# telemetria.net
KiCad netlist of a schematic drawn in EAGLE
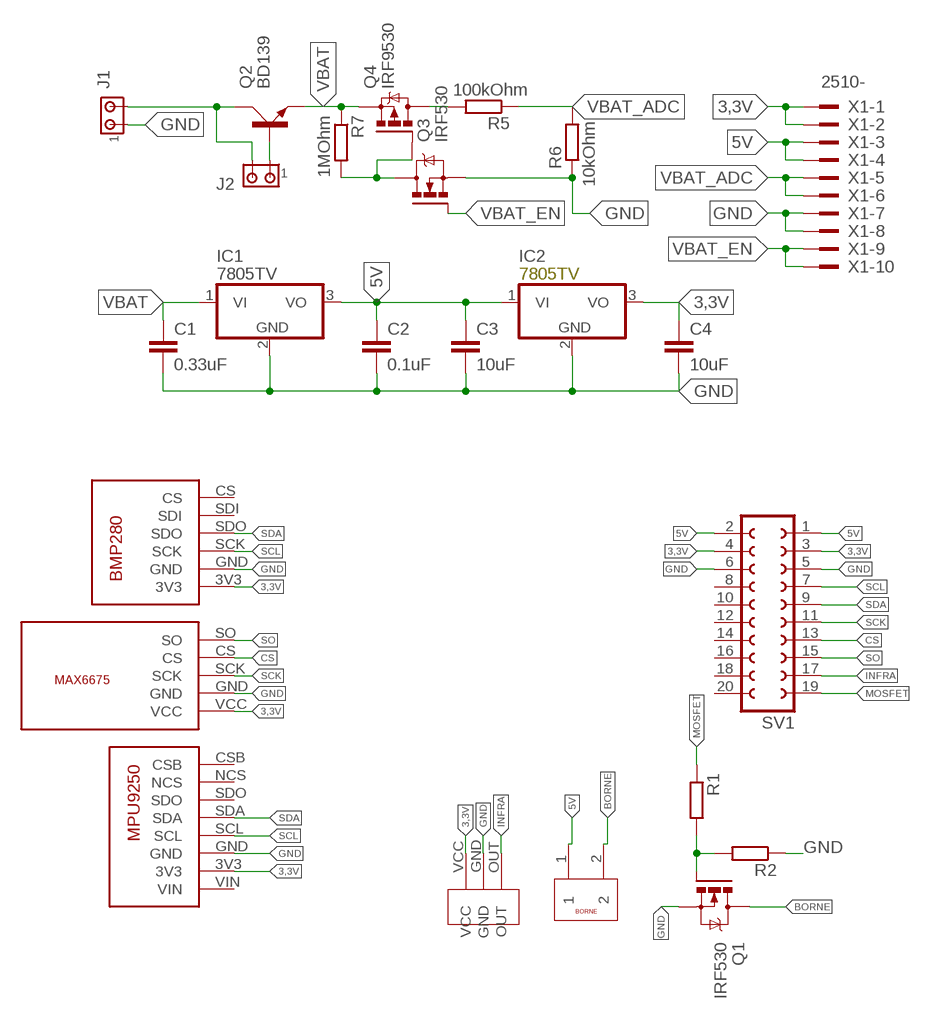
[diagram p0: schematic, sheet 1]

(export (version "E")
  (design (tool "Eeschema 10.0.6"))
  (components
    (comp (ref "C1")
      (value "0.33uF")
      (footprint "eagle-import:C2.5-3")
      (libsource (lib "eagle-import") (part "C2,5-3"))
    )
    (comp (ref "C2")
      (value "0.1uF")
      (footprint "eagle-import:C2.5-3")
      (libsource (lib "eagle-import") (part "C2,5-3"))
    )
    (comp (ref "C3")
      (value "10uF")
      (footprint "eagle-import:C2.5-3")
      (libsource (lib "eagle-import") (part "C2,5-3"))
    )
    (comp (ref "C4")
      (value "10uF")
      (footprint "eagle-import:C2.5-3")
      (libsource (lib "eagle-import") (part "C2,5-3"))
    )
    (comp (ref "IC1")
      (value "7805TV")
      (footprint "eagle-import:TO220V")
      (libsource (lib "eagle-import") (part "78TV05"))
    )
    (comp (ref "IC2")
      (value "7805TV")
      (footprint "eagle-import:TO220V")
      (libsource (lib "eagle-import") (part "78TV05"))
    )
    (comp (ref "J1")
      (value "MTA02-156")
      (footprint "eagle-import:1X2MTA")
      (libsource (lib "eagle-import") (part "MTA02-156"))
    )
    (comp (ref "J2")
      (value "MTA02-100")
      (footprint "eagle-import:10X02MTA")
      (libsource (lib "eagle-import") (part "MTA02-100"))
    )
    (comp (ref "Q1")
      (value "IRF530")
      (footprint "eagle-import:TO220BV")
      (libsource (lib "eagle-import") (part "IRF530"))
    )
    (comp (ref "Q2")
      (value "BD139")
      (footprint "eagle-import:TO126AV")
      (libsource (lib "eagle-import") (part "BD139"))
    )
    (comp (ref "Q3")
      (value "IRF530")
      (footprint "eagle-import:TO220BV")
      (libsource (lib "eagle-import") (part "IRF530"))
    )
    (comp (ref "Q4")
      (value "IRF9530")
      (footprint "eagle-import:TO220BV")
      (libsource (lib "eagle-import") (part "IRF9530"))
    )
    (comp (ref "R1")
      (value "R-EU_0204/7")
      (footprint "eagle-import:0204_7")
      (libsource (lib "eagle-import") (part "R-EU_0204/7"))
    )
    (comp (ref "R2")
      (value "R-EU_0207/10")
      (footprint "eagle-import:0207_10")
      (libsource (lib "eagle-import") (part "R-EU_0207/10"))
    )
    (comp (ref "R5")
      (value "100kOhm")
      (footprint "eagle-import:0207_10")
      (libsource (lib "eagle-import") (part "R-EU_0207/10"))
    )
    (comp (ref "R6")
      (value "10kOhm")
      (footprint "eagle-import:0207_10")
      (libsource (lib "eagle-import") (part "R-EU_0207/10"))
    )
    (comp (ref "R7")
      (value "1MOhm")
      (footprint "eagle-import:0207_10")
      (libsource (lib "eagle-import") (part "R-EU_0207/10"))
    )
    (comp (ref "SV1")
      (value "FE10-2")
      (footprint "eagle-import:FE10-2")
      (libsource (lib "eagle-import") (part "FE10-2"))
    )
    (comp (ref "U$1")
      (value "BMP280")
      (footprint "eagle-import:BMP280")
      (libsource (lib "eagle-import") (part "BMP280"))
    )
    (comp (ref "U$2")
      (value "MAX6675")
      (footprint "eagle-import:MAX6675")
      (libsource (lib "eagle-import") (part "MAX6675"))
    )
    (comp (ref "U$3")
      (value "MPU9250")
      (footprint "eagle-import:MP9250")
      (libsource (lib "eagle-import") (part "MPU9250"))
    )
    (comp (ref "U$4")
      (value "PIN-INFRA")
      (footprint "eagle-import:PIN-INFRA")
      (libsource (lib "eagle-import") (part "PIN-INFRA"))
    )
    (comp (ref "U$5")
      (value "BORNE")
      (footprint "eagle-import:BORNE")
      (libsource (lib "eagle-import") (part "BORNE"))
    )
    (comp (ref "X1")
      (value "2510-")
      (footprint "eagle-import:PAK100_2500-10")
      (fields (field (name "MF") "3M") (field (name "MPN") "2510-6002UB"))
      (libsource (lib "eagle-import") (part "2510-"))
    )
  )
  (nets
    (net (code "1") (name "3,3V") (class "Default")
      (node (ref "C4") (pin "1") (pinfunction "1_1") (pintype "passive"))
      (node (ref "IC2") (pin "3") (pinfunction "VO_3") (pintype "passive"))
      (node (ref "SV1") (pin "3") (pinfunction "3_3") (pintype "passive"))
      (node (ref "SV1") (pin "4") (pinfunction "4_4") (pintype "passive"))
      (node (ref "U$1") (pin "3V3") (pinfunction "3V3_3V3") (pintype "bidirectional"))
      (node (ref "U$2") (pin "VCC") (pinfunction "VCC_VCC") (pintype "bidirectional"))
      (node (ref "U$3") (pin "3V3") (pinfunction "3V3_3V3") (pintype "bidirectional"))
      (node (ref "U$4") (pin "VCC") (pinfunction "VCC_VCC") (pintype "bidirectional"))
      (node (ref "X1") (pin "1") (pinfunction "KL_1") (pintype "passive"))
      (node (ref "X1") (pin "2") (pinfunction "KL_2") (pintype "passive"))
    )
    (net (code "2") (name "5V") (class "Default")
      (node (ref "C2") (pin "1") (pinfunction "1_1") (pintype "passive"))
      (node (ref "C3") (pin "1") (pinfunction "1_1") (pintype "passive"))
      (node (ref "IC1") (pin "3") (pinfunction "VO_3") (pintype "passive"))
      (node (ref "IC2") (pin "1") (pinfunction "VI_1") (pintype "input"))
      (node (ref "SV1") (pin "1") (pinfunction "1_1") (pintype "passive"))
      (node (ref "SV1") (pin "2") (pinfunction "2_2") (pintype "passive"))
      (node (ref "U$5") (pin "1") (pinfunction "1_1") (pintype "bidirectional"))
      (node (ref "X1") (pin "3") (pinfunction "KL_3") (pintype "passive"))
      (node (ref "X1") (pin "4") (pinfunction "KL_4") (pintype "passive"))
    )
    (net (code "3") (name "BORNE") (class "Default")
      (node (ref "Q1") (pin "D") (pinfunction "D_D") (pintype "passive"))
      (node (ref "U$5") (pin "2") (pinfunction "2_2") (pintype "bidirectional"))
    )
    (net (code "4") (name "CS") (class "Default")
      (node (ref "SV1") (pin "13") (pinfunction "13_13") (pintype "passive"))
      (node (ref "U$2") (pin "CS") (pinfunction "CS_CS") (pintype "bidirectional"))
    )
    (net (code "5") (name "GND") (class "Default")
      (node (ref "C1") (pin "2") (pinfunction "2_2") (pintype "passive"))
      (node (ref "C2") (pin "2") (pinfunction "2_2") (pintype "passive"))
      (node (ref "C3") (pin "2") (pinfunction "2_2") (pintype "passive"))
      (node (ref "C4") (pin "2") (pinfunction "2_2") (pintype "passive"))
      (node (ref "IC1") (pin "2") (pinfunction "GND_2") (pintype "passive"))
      (node (ref "IC2") (pin "2") (pinfunction "GND_2") (pintype "passive"))
      (node (ref "J1") (pin "1") (pinfunction "1_1") (pintype "passive"))
      (node (ref "Q1") (pin "S") (pinfunction "S_S") (pintype "passive"))
      (node (ref "Q3") (pin "S") (pinfunction "S_S") (pintype "passive"))
      (node (ref "R2") (pin "1") (pinfunction "1_1") (pintype "passive"))
      (node (ref "R6") (pin "1") (pinfunction "1_1") (pintype "passive"))
      (node (ref "SV1") (pin "5") (pinfunction "5_5") (pintype "passive"))
      (node (ref "SV1") (pin "6") (pinfunction "6_6") (pintype "passive"))
      (node (ref "U$1") (pin "GND") (pinfunction "GND_GND") (pintype "bidirectional"))
      (node (ref "U$2") (pin "GND") (pinfunction "GND_GND") (pintype "bidirectional"))
      (node (ref "U$3") (pin "GND") (pinfunction "GND_GND") (pintype "bidirectional"))
      (node (ref "U$4") (pin "GND") (pinfunction "GND_GND") (pintype "bidirectional"))
      (node (ref "X1") (pin "7") (pinfunction "KL_7") (pintype "passive"))
      (node (ref "X1") (pin "8") (pinfunction "KL_8") (pintype "passive"))
    )
    (net (code "6") (name "INFRA") (class "Default")
      (node (ref "SV1") (pin "17") (pinfunction "17_17") (pintype "passive"))
      (node (ref "U$4") (pin "OUT") (pinfunction "OUT_OUT") (pintype "bidirectional"))
    )
    (net (code "7") (name "MOSFET") (class "Default")
      (node (ref "Q1") (pin "G") (pinfunction "G_G") (pintype "passive"))
      (node (ref "R1") (pin "1") (pinfunction "1_1") (pintype "passive"))
      (node (ref "R1") (pin "2") (pinfunction "2_2") (pintype "passive"))
      (node (ref "R2") (pin "2") (pinfunction "2_2") (pintype "passive"))
      (node (ref "SV1") (pin "19") (pinfunction "19_19") (pintype "passive"))
    )
    (net (code "8") (name "Net-(J1-Pad2)") (class "Default")
      (node (ref "J1") (pin "2") (pinfunction "2_2") (pintype "passive"))
      (node (ref "J2") (pin "2") (pinfunction "2_2") (pintype "passive"))
      (node (ref "Q2") (pin "C") (pinfunction "C_C") (pintype "passive"))
    )
    (net (code "9") (name "Net-(J2-Pad1)") (class "Default")
      (node (ref "J2") (pin "1") (pinfunction "1_1") (pintype "passive"))
      (node (ref "Q2") (pin "B") (pinfunction "B_B") (pintype "passive"))
    )
    (net (code "10") (name "Net-(Q3-PadD)") (class "Default")
      (node (ref "Q3") (pin "D") (pinfunction "D_D") (pintype "passive"))
      (node (ref "Q4") (pin "G") (pinfunction "G_G") (pintype "passive"))
      (node (ref "R7") (pin "2") (pinfunction "2_2") (pintype "passive"))
    )
    (net (code "11") (name "Net-(Q4-PadD)") (class "Default")
      (node (ref "Q4") (pin "D") (pinfunction "D_D") (pintype "passive"))
      (node (ref "R5") (pin "2") (pinfunction "2_2") (pintype "passive"))
    )
    (net (code "12") (name "SCK") (class "Default")
      (node (ref "SV1") (pin "11") (pinfunction "11_11") (pintype "passive"))
      (node (ref "U$2") (pin "SCK") (pinfunction "SCK_SCK") (pintype "bidirectional"))
    )
    (net (code "13") (name "SCL") (class "Default")
      (node (ref "SV1") (pin "7") (pinfunction "7_7") (pintype "passive"))
      (node (ref "U$1") (pin "SCK") (pinfunction "SCK_SCK") (pintype "bidirectional"))
      (node (ref "U$3") (pin "SCL") (pinfunction "SCL_SCL") (pintype "bidirectional"))
    )
    (net (code "14") (name "SDA") (class "Default")
      (node (ref "SV1") (pin "9") (pinfunction "9_9") (pintype "passive"))
      (node (ref "U$1") (pin "SDO") (pinfunction "SDO_SDO") (pintype "bidirectional"))
      (node (ref "U$3") (pin "SDA") (pinfunction "SDA_SDA") (pintype "bidirectional"))
    )
    (net (code "15") (name "SO") (class "Default")
      (node (ref "SV1") (pin "15") (pinfunction "15_15") (pintype "passive"))
      (node (ref "U$2") (pin "SO") (pinfunction "SO_SO") (pintype "bidirectional"))
    )
    (net (code "16") (name "VBAT") (class "Default")
      (node (ref "C1") (pin "1") (pinfunction "1_1") (pintype "passive"))
      (node (ref "IC1") (pin "1") (pinfunction "VI_1") (pintype "input"))
      (node (ref "Q2") (pin "E") (pinfunction "E_E") (pintype "passive"))
      (node (ref "Q4") (pin "S") (pinfunction "S_S") (pintype "passive"))
      (node (ref "R7") (pin "1") (pinfunction "1_1") (pintype "passive"))
    )
    (net (code "17") (name "VBAT_ADC") (class "Default")
      (node (ref "R5") (pin "1") (pinfunction "1_1") (pintype "passive"))
      (node (ref "R6") (pin "2") (pinfunction "2_2") (pintype "passive"))
      (node (ref "X1") (pin "5") (pinfunction "KL_5") (pintype "passive"))
      (node (ref "X1") (pin "6") (pinfunction "KL_6") (pintype "passive"))
    )
    (net (code "18") (name "VBAT_EN") (class "Default")
      (node (ref "Q3") (pin "G") (pinfunction "G_G") (pintype "passive"))
      (node (ref "X1") (pin "10") (pinfunction "KL_10") (pintype "passive"))
      (node (ref "X1") (pin "9") (pinfunction "KL_9") (pintype "passive"))
    )
    (net (code "19") (name "unconnected-(SV1-Pad8)") (class "Default")
      (node (ref "SV1") (pin "8") (pinfunction "8_8") (pintype "passive"))
    )
    (net (code "20") (name "unconnected-(SV1-Pad10)") (class "Default")
      (node (ref "SV1") (pin "10") (pinfunction "10_10") (pintype "passive"))
    )
    (net (code "21") (name "unconnected-(SV1-Pad12)") (class "Default")
      (node (ref "SV1") (pin "12") (pinfunction "12_12") (pintype "passive"))
    )
    (net (code "22") (name "unconnected-(SV1-Pad14)") (class "Default")
      (node (ref "SV1") (pin "14") (pinfunction "14_14") (pintype "passive"))
    )
    (net (code "23") (name "unconnected-(SV1-Pad16)") (class "Default")
      (node (ref "SV1") (pin "16") (pinfunction "16_16") (pintype "passive"))
    )
    (net (code "24") (name "unconnected-(SV1-Pad18)") (class "Default")
      (node (ref "SV1") (pin "18") (pinfunction "18_18") (pintype "passive"))
    )
    (net (code "25") (name "unconnected-(SV1-Pad20)") (class "Default")
      (node (ref "SV1") (pin "20") (pinfunction "20_20") (pintype "passive"))
    )
    (net (code "26") (name "unconnected-(U$1-PadCS)") (class "Default")
      (node (ref "U$1") (pin "CS") (pinfunction "CS_CS") (pintype "bidirectional"))
    )
    (net (code "27") (name "unconnected-(U$1-PadSDI)") (class "Default")
      (node (ref "U$1") (pin "SDI") (pinfunction "SDI_SDI") (pintype "bidirectional"))
    )
    (net (code "28") (name "unconnected-(U$3-PadCSB)") (class "Default")
      (node (ref "U$3") (pin "CSB") (pinfunction "CSB_CSB") (pintype "bidirectional"))
    )
    (net (code "29") (name "unconnected-(U$3-PadNCS)") (class "Default")
      (node (ref "U$3") (pin "NCS") (pinfunction "NCS_NCS") (pintype "bidirectional"))
    )
    (net (code "30") (name "unconnected-(U$3-PadSDO)") (class "Default")
      (node (ref "U$3") (pin "SDO") (pinfunction "SDO_SDO") (pintype "bidirectional"))
    )
    (net (code "31") (name "unconnected-(U$3-PadVIN)") (class "Default")
      (node (ref "U$3") (pin "VIN") (pinfunction "VIN_VIN") (pintype "bidirectional"))
    )
  )
)
